# JST2_switch.net
KiCad netlist of a schematic drawn in EAGLE
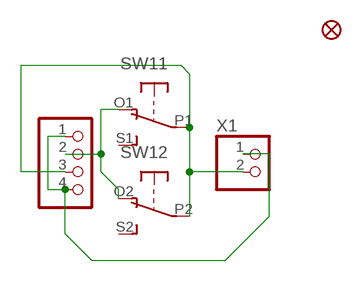
[diagram p0: schematic, sheet 1]

(export (version "E")
  (design (tool "Eeschema 10.0.6"))
  (components
    (comp (ref "FID1")
      (value "FIDUCIAL\"\"")
      (footprint "eagle-import:FIDUCIAL_1MM")
      (libsource (lib "eagle-import") (part "FIDUCIAL{dblquote}{dblquote}"))
    )
    (comp (ref "JP1")
      (value "PADS-4")
      (footprint "eagle-import:PADS-4")
      (libsource (lib "eagle-import") (part "PADS-4"))
    )
    (comp (ref "SW1")
      (value "DPDT-EG1390")
      (footprint "eagle-import:EG1390")
      (libsource (lib "eagle-import") (part "DPDT-EG1390"))
    )
    (comp (ref "X1")
      (value "CON_JST_PH_2PIN")
      (footprint "eagle-import:JSTPH2")
      (libsource (lib "eagle-import") (part "CON_JST_PH_2PIN"))
    )
  )
  (nets
    (net (code "1") (name "Net-(JP1-Pad1)") (class "Default")
      (node (ref "JP1") (pin "1") (pinfunction "1_1") (pintype "passive"))
      (node (ref "JP1") (pin "4") (pinfunction "4_4") (pintype "passive"))
      (node (ref "X1") (pin "1") (pinfunction "1_1") (pintype "passive"))
    )
    (net (code "2") (name "Net-(SW1A-O)") (class "Default")
      (node (ref "JP1") (pin "2") (pinfunction "2_2") (pintype "passive"))
      (node (ref "SW1") (pin "O1") (pinfunction "O_O1") (pintype "passive"))
      (node (ref "SW1") (pin "O2") (pinfunction "O_O2") (pintype "passive"))
    )
    (net (code "3") (name "Net-(SW1A-P)") (class "Default")
      (node (ref "JP1") (pin "3") (pinfunction "3_3") (pintype "passive"))
      (node (ref "SW1") (pin "P1") (pinfunction "P_P1") (pintype "passive"))
      (node (ref "SW1") (pin "P2") (pinfunction "P_P2") (pintype "passive"))
      (node (ref "X1") (pin "2") (pinfunction "2_2") (pintype "passive"))
    )
    (net (code "4") (name "unconnected-(SW1A-S-PadS1)") (class "Default")
      (node (ref "SW1") (pin "S1") (pinfunction "S_S1") (pintype "passive"))
    )
    (net (code "5") (name "unconnected-(SW1B-S-PadS2)") (class "Default")
      (node (ref "SW1") (pin "S2") (pinfunction "S_S2") (pintype "passive"))
    )
  )
)
